# Logic_probe.net
KiCad netlist of a schematic drawn in EAGLE
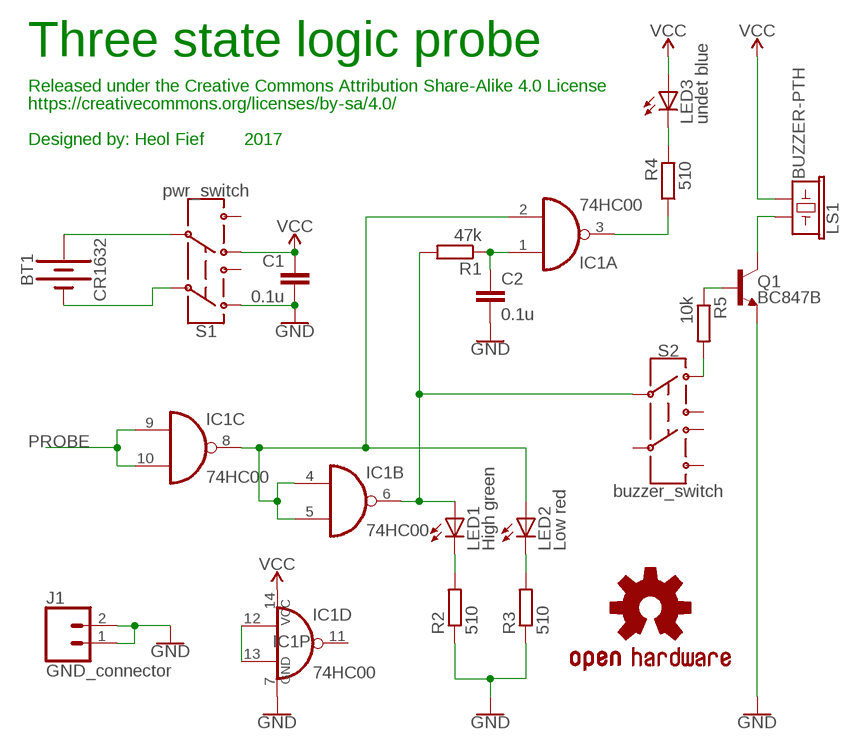
[diagram p0: schematic, sheet 1]

(export (version "E")
  (design (tool "Eeschema 10.0.6"))
  (components
    (comp (ref "BT1")
      (value "CR1632")
      (footprint "eagle-import:BATTCON_16MM_PTH")
      (libsource (lib "eagle-import") (part "BATTERY-16MM_PTH"))
    )
    (comp (ref "C1")
      (value "0.1u")
      (footprint "eagle-import:C0805")
      (libsource (lib "eagle-import") (part "C-EUC0805"))
    )
    (comp (ref "C2")
      (value "0.1u")
      (footprint "eagle-import:C0805")
      (libsource (lib "eagle-import") (part "C-EUC0805"))
    )
    (comp (ref "IC1")
      (value "74HC00")
      (footprint "eagle-import:SO14")
      (libsource (lib "eagle-import") (part "7400DHC"))
    )
    (comp (ref "J1")
      (value "GND_connector")
      (footprint "eagle-import:MOLEX-1X2")
      (libsource (lib "eagle-import") (part "CONN_02POLAR"))
    )
    (comp (ref "LED1")
      (value "High green")
      (footprint "eagle-import:1206")
      (libsource (lib "eagle-import") (part "LEDSMT1206"))
    )
    (comp (ref "LED2")
      (value "Low red")
      (footprint "eagle-import:1206")
      (libsource (lib "eagle-import") (part "LEDSMT1206"))
    )
    (comp (ref "LED3")
      (value "undet blue")
      (footprint "eagle-import:1206")
      (libsource (lib "eagle-import") (part "LEDSMT1206"))
    )
    (comp (ref "LOGO1")
      (value "OSHW-LOGOL")
      (footprint "eagle-import:OSHW-LOGO-L")
      (libsource (lib "eagle-import") (part "OSHW-LOGOL"))
    )
    (comp (ref "LS1")
      (value "BUZZER-PTH")
      (footprint "eagle-import:BUZZER-12MM")
      (libsource (lib "eagle-import") (part "BUZZER-PTH"))
    )
    (comp (ref "Q1")
      (value "BC847B")
      (footprint "eagle-import:SOT23-3")
      (libsource (lib "eagle-import") (part "TRANS_NPN-MMBT2222AL"))
    )
    (comp (ref "R1")
      (value "47k")
      (footprint "eagle-import:R1206")
      (libsource (lib "eagle-import") (part "R-EU_R1206"))
    )
    (comp (ref "R2")
      (value "510")
      (footprint "eagle-import:R0805")
      (libsource (lib "eagle-import") (part "R-EU_R0805"))
    )
    (comp (ref "R3")
      (value "510")
      (footprint "eagle-import:R0805")
      (libsource (lib "eagle-import") (part "R-EU_R0805"))
    )
    (comp (ref "R4")
      (value "510")
      (footprint "eagle-import:R0805")
      (libsource (lib "eagle-import") (part "R-EU_R0805"))
    )
    (comp (ref "R5")
      (value "10k")
      (footprint "eagle-import:R0805")
      (libsource (lib "eagle-import") (part "R-EU_R0805"))
    )
    (comp (ref "S1")
      (value "pwr_switch")
      (footprint "eagle-import:SWITCH_DPDT_SMD_AYZ0202")
      (libsource (lib "eagle-import") (part "SWITCH-DPDT-SMD-AYZ0202"))
    )
    (comp (ref "S2")
      (value "buzzer_switch")
      (footprint "eagle-import:SWITCH_DPDT_SMD_AYZ0202")
      (libsource (lib "eagle-import") (part "SWITCH-DPDT-SMD-AYZ0202"))
    )
  )
  (nets
    (net (code "1") (name "/PROBE") (class "Default")
      (node (ref "IC1") (pin "10") (pinfunction "I1_10") (pintype "input"))
      (node (ref "IC1") (pin "9") (pinfunction "I0_9") (pintype "input"))
    )
    (net (code "2") (name "GND") (class "Default")
      (node (ref "C1") (pin "2") (pinfunction "2_2") (pintype "passive"))
      (node (ref "C2") (pin "2") (pinfunction "2_2") (pintype "passive"))
      (node (ref "IC1") (pin "7") (pinfunction "GND_7") (pintype "power_in"))
      (node (ref "J1") (pin "1") (pinfunction "1_1") (pintype "passive"))
      (node (ref "J1") (pin "2") (pinfunction "2_2") (pintype "passive"))
      (node (ref "Q1") (pin "2") (pinfunction "E_2") (pintype "passive"))
      (node (ref "R2") (pin "1") (pinfunction "1_1") (pintype "passive"))
      (node (ref "R3") (pin "1") (pinfunction "1_1") (pintype "passive"))
      (node (ref "S1") (pin "1") (pinfunction "1_1") (pintype "bidirectional"))
    )
    (net (code "3") (name "Net-(BT1-+-PadVCC@1)") (class "Default")
      (node (ref "BT1") (pin "VCC@1") (pinfunction "+_VCC@1") (pintype "power_in"))
      (node (ref "BT1") (pin "VCC@2") (pinfunction "+_VCC@2") (pintype "power_in"))
      (node (ref "S1") (pin "5") (pinfunction "5_5") (pintype "bidirectional"))
    )
    (net (code "4") (name "Net-(BT1--)") (class "Default")
      (node (ref "BT1") (pin "GND") (pinfunction "-_GND") (pintype "power_in"))
      (node (ref "S1") (pin "2") (pinfunction "2_2") (pintype "bidirectional"))
    )
    (net (code "5") (name "Net-(IC1A-I0)") (class "Default")
      (node (ref "C2") (pin "1") (pinfunction "1_1") (pintype "passive"))
      (node (ref "IC1") (pin "1") (pinfunction "I0_1") (pintype "input"))
      (node (ref "R1") (pin "1") (pinfunction "1_1") (pintype "passive"))
    )
    (net (code "6") (name "Net-(IC1A-I1)") (class "Default")
      (node (ref "IC1") (pin "2") (pinfunction "I1_2") (pintype "input"))
      (node (ref "IC1") (pin "4") (pinfunction "I0_4") (pintype "input"))
      (node (ref "IC1") (pin "5") (pinfunction "I1_5") (pintype "input"))
      (node (ref "IC1") (pin "8") (pinfunction "O_8") (pintype "output"))
      (node (ref "LED2") (pin "A") (pinfunction "A_A") (pintype "passive"))
    )
    (net (code "7") (name "Net-(IC1A-O)") (class "Default")
      (node (ref "IC1") (pin "3") (pinfunction "O_3") (pintype "output"))
      (node (ref "R4") (pin "1") (pinfunction "1_1") (pintype "passive"))
    )
    (net (code "8") (name "Net-(IC1B-O)") (class "Default")
      (node (ref "IC1") (pin "6") (pinfunction "O_6") (pintype "output"))
      (node (ref "LED1") (pin "A") (pinfunction "A_A") (pintype "passive"))
      (node (ref "R1") (pin "2") (pinfunction "2_2") (pintype "passive"))
      (node (ref "S2") (pin "2") (pinfunction "2_2") (pintype "bidirectional"))
    )
    (net (code "9") (name "Net-(IC1D-I0)") (class "Default")
      (node (ref "IC1") (pin "12") (pinfunction "I0_12") (pintype "input"))
      (node (ref "IC1") (pin "13") (pinfunction "I1_13") (pintype "input"))
    )
    (net (code "10") (name "Net-(LED1-PadC)") (class "Default")
      (node (ref "LED1") (pin "C") (pinfunction "C_C") (pintype "passive"))
      (node (ref "R2") (pin "2") (pinfunction "2_2") (pintype "passive"))
    )
    (net (code "11") (name "Net-(LED2-PadC)") (class "Default")
      (node (ref "LED2") (pin "C") (pinfunction "C_C") (pintype "passive"))
      (node (ref "R3") (pin "2") (pinfunction "2_2") (pintype "passive"))
    )
    (net (code "12") (name "Net-(LED3-PadC)") (class "Default")
      (node (ref "LED3") (pin "C") (pinfunction "C_C") (pintype "passive"))
      (node (ref "R4") (pin "2") (pinfunction "2_2") (pintype "passive"))
    )
    (net (code "13") (name "Net-(LS1-1)") (class "Default")
      (node (ref "LS1") (pin "+") (pinfunction "1_+") (pintype "passive"))
      (node (ref "Q1") (pin "3") (pinfunction "C_3") (pintype "passive"))
    )
    (net (code "14") (name "Net-(Q1-B)") (class "Default")
      (node (ref "Q1") (pin "1") (pinfunction "B_1") (pintype "passive"))
      (node (ref "R5") (pin "1") (pinfunction "1_1") (pintype "passive"))
    )
    (net (code "15") (name "Net-(R5-Pad2)") (class "Default")
      (node (ref "R5") (pin "2") (pinfunction "2_2") (pintype "passive"))
      (node (ref "S2") (pin "1") (pinfunction "1_1") (pintype "bidirectional"))
    )
    (net (code "16") (name "VCC") (class "Default")
      (node (ref "C1") (pin "1") (pinfunction "1_1") (pintype "passive"))
      (node (ref "IC1") (pin "14") (pinfunction "VCC_14") (pintype "power_in"))
      (node (ref "LED3") (pin "A") (pinfunction "A_A") (pintype "passive"))
      (node (ref "LS1") (pin "-") (pinfunction "2_-") (pintype "passive"))
      (node (ref "S1") (pin "4") (pinfunction "4_4") (pintype "bidirectional"))
    )
    (net (code "17") (name "unconnected-(IC1D-O-Pad11)") (class "Default")
      (node (ref "IC1") (pin "11") (pinfunction "O_11") (pintype "output"))
    )
    (net (code "18") (name "unconnected-(S1-Pad3)") (class "Default")
      (node (ref "S1") (pin "3") (pinfunction "3_3") (pintype "bidirectional"))
    )
    (net (code "19") (name "unconnected-(S1-Pad6)") (class "Default")
      (node (ref "S1") (pin "6") (pinfunction "6_6") (pintype "bidirectional"))
    )
    (net (code "20") (name "unconnected-(S2-Pad3)") (class "Default")
      (node (ref "S2") (pin "3") (pinfunction "3_3") (pintype "bidirectional"))
    )
    (net (code "21") (name "unconnected-(S2-Pad4)") (class "Default")
      (node (ref "S2") (pin "4") (pinfunction "4_4") (pintype "bidirectional"))
    )
    (net (code "22") (name "unconnected-(S2-Pad5)") (class "Default")
      (node (ref "S2") (pin "5") (pinfunction "5_5") (pintype "bidirectional"))
    )
    (net (code "23") (name "unconnected-(S2-Pad6)") (class "Default")
      (node (ref "S2") (pin "6") (pinfunction "6_6") (pintype "bidirectional"))
    )
  )
)
